# driver_ckt_3.net
KiCad netlist of a schematic drawn in EAGLE
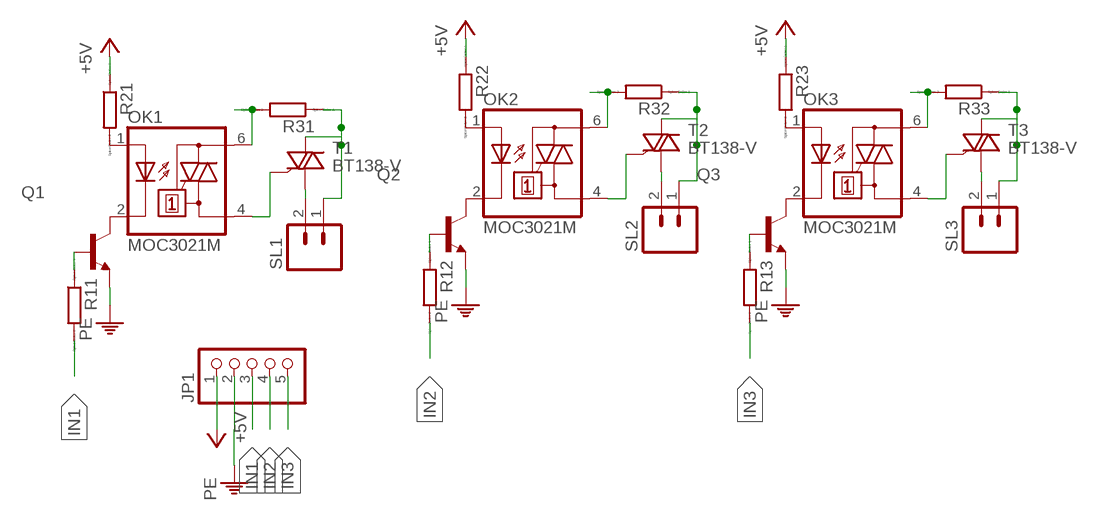
[diagram p0: schematic, sheet 1]

(export (version "E")
  (design (tool "Eeschema 10.0.6"))
  (components
    (comp (ref "JP1")
      (value "PINHD-1X5")
      (footprint "eagle-import:1X05")
      (libsource (lib "eagle-import") (part "PINHD-1X5"))
    )
    (comp (ref "OK1")
      (value "MOC3021M")
      (footprint "eagle-import:DIL06")
      (fields (field (name "MF") "FAIRCHILD SEMICONDUCTOR") (field (name "MPN") "MOC3021-M"))
      (libsource (lib "eagle-import") (part "MOC30M21"))
    )
    (comp (ref "OK2")
      (value "MOC3021M")
      (footprint "eagle-import:DIL06")
      (fields (field (name "MF") "FAIRCHILD SEMICONDUCTOR") (field (name "MPN") "MOC3021-M"))
      (libsource (lib "eagle-import") (part "MOC30M21"))
    )
    (comp (ref "OK3")
      (value "MOC3021M")
      (footprint "eagle-import:DIL06")
      (fields (field (name "MF") "FAIRCHILD SEMICONDUCTOR") (field (name "MPN") "MOC3021-M"))
      (libsource (lib "eagle-import") (part "MOC30M21"))
    )
    (comp (ref "Q1")
      (value "-NPN-SOT23-EBC")
      (footprint "eagle-import:SOT23-EBC")
      (libsource (lib "eagle-import") (part "-NPN-SOT23-EBC"))
    )
    (comp (ref "Q2")
      (value "-NPN-SOT23-EBC")
      (footprint "eagle-import:SOT23-EBC")
      (libsource (lib "eagle-import") (part "-NPN-SOT23-EBC"))
    )
    (comp (ref "Q3")
      (value "-NPN-SOT23-EBC")
      (footprint "eagle-import:SOT23-EBC")
      (libsource (lib "eagle-import") (part "-NPN-SOT23-EBC"))
    )
    (comp (ref "R11")
      (value "RR1206")
      (footprint "eagle-import:R1206")
      (libsource (lib "eagle-import") (part "RR1206"))
    )
    (comp (ref "R12")
      (value "RR1206")
      (footprint "eagle-import:R1206")
      (libsource (lib "eagle-import") (part "RR1206"))
    )
    (comp (ref "R13")
      (value "RR1206")
      (footprint "eagle-import:R1206")
      (libsource (lib "eagle-import") (part "RR1206"))
    )
    (comp (ref "R21")
      (value "RR1206")
      (footprint "eagle-import:R1206")
      (libsource (lib "eagle-import") (part "RR1206"))
    )
    (comp (ref "R22")
      (value "RR1206")
      (footprint "eagle-import:R1206")
      (libsource (lib "eagle-import") (part "RR1206"))
    )
    (comp (ref "R23")
      (value "RR1206")
      (footprint "eagle-import:R1206")
      (libsource (lib "eagle-import") (part "RR1206"))
    )
    (comp (ref "R31")
      (value "RR1206")
      (footprint "eagle-import:R1206")
      (libsource (lib "eagle-import") (part "RR1206"))
    )
    (comp (ref "R32")
      (value "RR1206")
      (footprint "eagle-import:R1206")
      (libsource (lib "eagle-import") (part "RR1206"))
    )
    (comp (ref "R33")
      (value "RR1206")
      (footprint "eagle-import:R1206")
      (libsource (lib "eagle-import") (part "RR1206"))
    )
    (comp (ref "SL1")
      (value "M02")
      (footprint "eagle-import:02P")
      (libsource (lib "eagle-import") (part "M02"))
    )
    (comp (ref "SL2")
      (value "M02")
      (footprint "eagle-import:02P")
      (libsource (lib "eagle-import") (part "M02"))
    )
    (comp (ref "SL3")
      (value "M02")
      (footprint "eagle-import:02P")
      (libsource (lib "eagle-import") (part "M02"))
    )
    (comp (ref "T1")
      (value "BT138-V")
      (footprint "eagle-import:TO220BV")
      (libsource (lib "eagle-import") (part "BT138-V"))
    )
    (comp (ref "T2")
      (value "BT138-V")
      (footprint "eagle-import:TO220BV")
      (libsource (lib "eagle-import") (part "BT138-V"))
    )
    (comp (ref "T3")
      (value "BT138-V")
      (footprint "eagle-import:TO220BV")
      (libsource (lib "eagle-import") (part "BT138-V"))
    )
  )
  (nets
    (net (code "1") (name "+5V") (class "Default")
      (node (ref "JP1") (pin "1") (pinfunction "1_1") (pintype "passive"))
      (node (ref "R21") (pin "1") (pinfunction "1_1") (pintype "passive"))
      (node (ref "R22") (pin "1") (pinfunction "1_1") (pintype "passive"))
      (node (ref "R23") (pin "1") (pinfunction "1_1") (pintype "passive"))
    )
    (net (code "2") (name "IN1") (class "Default")
      (node (ref "JP1") (pin "3") (pinfunction "3_3") (pintype "passive"))
      (node (ref "R11") (pin "2") (pinfunction "2_2") (pintype "passive"))
    )
    (net (code "3") (name "IN2") (class "Default")
      (node (ref "JP1") (pin "4") (pinfunction "4_4") (pintype "passive"))
      (node (ref "R12") (pin "2") (pinfunction "2_2") (pintype "passive"))
    )
    (net (code "4") (name "IN3") (class "Default")
      (node (ref "JP1") (pin "5") (pinfunction "5_5") (pintype "passive"))
      (node (ref "R13") (pin "2") (pinfunction "2_2") (pintype "passive"))
    )
    (net (code "5") (name "Net-(OK1-A)") (class "Default")
      (node (ref "OK1") (pin "1") (pinfunction "A_1") (pintype "passive"))
      (node (ref "R21") (pin "2") (pinfunction "2_2") (pintype "passive"))
    )
    (net (code "6") (name "Net-(OK1-A1)") (class "Default")
      (node (ref "OK1") (pin "4") (pinfunction "A1_4") (pintype "passive"))
      (node (ref "T1") (pin "G") (pinfunction "G_G") (pintype "passive"))
    )
    (net (code "7") (name "Net-(OK1-A2)") (class "Default")
      (node (ref "OK1") (pin "6") (pinfunction "A2_6") (pintype "passive"))
      (node (ref "R31") (pin "2") (pinfunction "2_2") (pintype "passive"))
    )
    (net (code "8") (name "Net-(OK1-C)") (class "Default")
      (node (ref "OK1") (pin "2") (pinfunction "C_2") (pintype "passive"))
      (node (ref "Q1") (pin "C") (pinfunction "C_C") (pintype "passive"))
    )
    (net (code "9") (name "Net-(OK2-A)") (class "Default")
      (node (ref "OK2") (pin "1") (pinfunction "A_1") (pintype "passive"))
      (node (ref "R22") (pin "2") (pinfunction "2_2") (pintype "passive"))
    )
    (net (code "10") (name "Net-(OK2-A1)") (class "Default")
      (node (ref "OK2") (pin "4") (pinfunction "A1_4") (pintype "passive"))
      (node (ref "T2") (pin "G") (pinfunction "G_G") (pintype "passive"))
    )
    (net (code "11") (name "Net-(OK2-A2)") (class "Default")
      (node (ref "OK2") (pin "6") (pinfunction "A2_6") (pintype "passive"))
      (node (ref "R32") (pin "2") (pinfunction "2_2") (pintype "passive"))
    )
    (net (code "12") (name "Net-(OK2-C)") (class "Default")
      (node (ref "OK2") (pin "2") (pinfunction "C_2") (pintype "passive"))
      (node (ref "Q2") (pin "C") (pinfunction "C_C") (pintype "passive"))
    )
    (net (code "13") (name "Net-(OK3-A)") (class "Default")
      (node (ref "OK3") (pin "1") (pinfunction "A_1") (pintype "passive"))
      (node (ref "R23") (pin "2") (pinfunction "2_2") (pintype "passive"))
    )
    (net (code "14") (name "Net-(OK3-A1)") (class "Default")
      (node (ref "OK3") (pin "4") (pinfunction "A1_4") (pintype "passive"))
      (node (ref "T3") (pin "G") (pinfunction "G_G") (pintype "passive"))
    )
    (net (code "15") (name "Net-(OK3-A2)") (class "Default")
      (node (ref "OK3") (pin "6") (pinfunction "A2_6") (pintype "passive"))
      (node (ref "R33") (pin "2") (pinfunction "2_2") (pintype "passive"))
    )
    (net (code "16") (name "Net-(OK3-C)") (class "Default")
      (node (ref "OK3") (pin "2") (pinfunction "C_2") (pintype "passive"))
      (node (ref "Q3") (pin "C") (pinfunction "C_C") (pintype "passive"))
    )
    (net (code "17") (name "Net-(Q1-PadB)") (class "Default")
      (node (ref "Q1") (pin "B") (pinfunction "B_B") (pintype "passive"))
      (node (ref "R11") (pin "1") (pinfunction "1_1") (pintype "passive"))
    )
    (net (code "18") (name "Net-(Q2-PadB)") (class "Default")
      (node (ref "Q2") (pin "B") (pinfunction "B_B") (pintype "passive"))
      (node (ref "R12") (pin "1") (pinfunction "1_1") (pintype "passive"))
    )
    (net (code "19") (name "Net-(Q3-PadB)") (class "Default")
      (node (ref "Q3") (pin "B") (pinfunction "B_B") (pintype "passive"))
      (node (ref "R13") (pin "1") (pinfunction "1_1") (pintype "passive"))
    )
    (net (code "20") (name "Net-(T1-A1)") (class "Default")
      (node (ref "SL1") (pin "2") (pinfunction "2_2") (pintype "passive"))
      (node (ref "T1") (pin "T1") (pinfunction "A1_T1") (pintype "passive"))
    )
    (net (code "21") (name "Net-(T1-A2)") (class "Default")
      (node (ref "R31") (pin "1") (pinfunction "1_1") (pintype "passive"))
      (node (ref "SL1") (pin "1") (pinfunction "1_1") (pintype "passive"))
      (node (ref "T1") (pin "T2") (pinfunction "A2_T2") (pintype "passive"))
    )
    (net (code "22") (name "Net-(T2-A1)") (class "Default")
      (node (ref "SL2") (pin "2") (pinfunction "2_2") (pintype "passive"))
      (node (ref "T2") (pin "T1") (pinfunction "A1_T1") (pintype "passive"))
    )
    (net (code "23") (name "Net-(T2-A2)") (class "Default")
      (node (ref "R32") (pin "1") (pinfunction "1_1") (pintype "passive"))
      (node (ref "SL2") (pin "1") (pinfunction "1_1") (pintype "passive"))
      (node (ref "T2") (pin "T2") (pinfunction "A2_T2") (pintype "passive"))
    )
    (net (code "24") (name "Net-(T3-A1)") (class "Default")
      (node (ref "SL3") (pin "2") (pinfunction "2_2") (pintype "passive"))
      (node (ref "T3") (pin "T1") (pinfunction "A1_T1") (pintype "passive"))
    )
    (net (code "25") (name "Net-(T3-A2)") (class "Default")
      (node (ref "R33") (pin "1") (pinfunction "1_1") (pintype "passive"))
      (node (ref "SL3") (pin "1") (pinfunction "1_1") (pintype "passive"))
      (node (ref "T3") (pin "T2") (pinfunction "A2_T2") (pintype "passive"))
    )
    (net (code "26") (name "PE") (class "Default")
      (node (ref "JP1") (pin "2") (pinfunction "2_2") (pintype "passive"))
      (node (ref "Q1") (pin "E") (pinfunction "E_E") (pintype "passive"))
      (node (ref "Q2") (pin "E") (pinfunction "E_E") (pintype "passive"))
      (node (ref "Q3") (pin "E") (pinfunction "E_E") (pintype "passive"))
    )
  )
)
